# SDI.net
KiCad netlist of a schematic drawn in Altium Designer
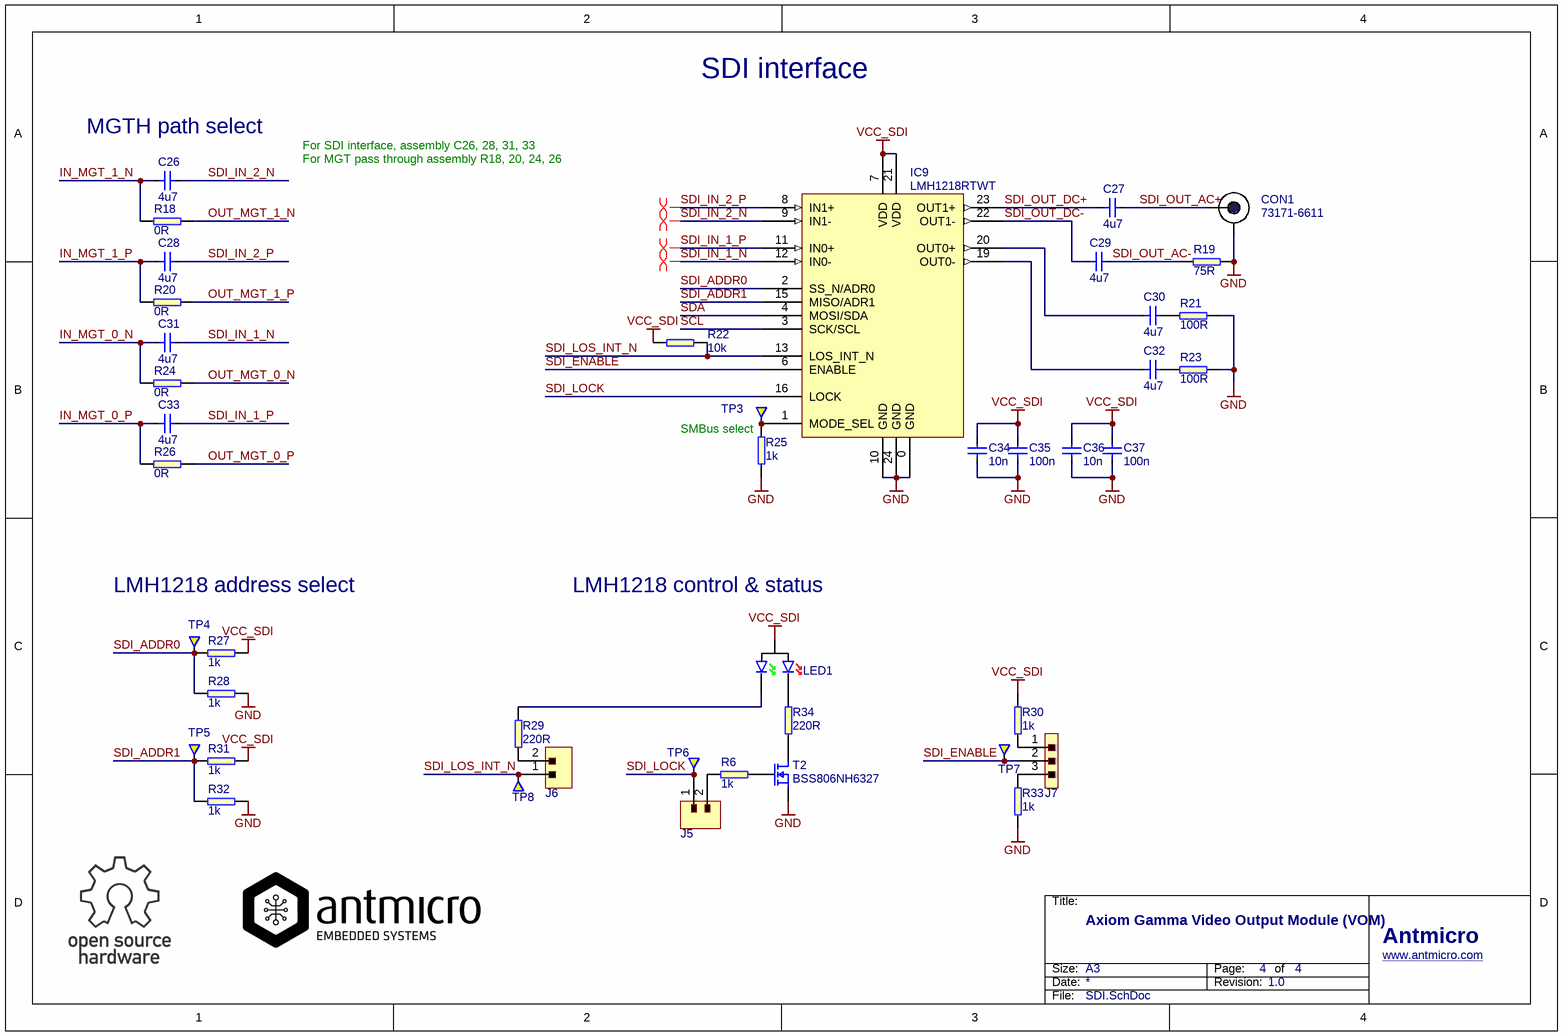
[diagram p0: SDI.SchDoc]

(export (version "E")
  (design (tool "Eeschema 10.0.6"))
  (components
    (comp (ref "C26")
      (value "4u7")
      (footprint "0402")
      (description "MLCC SMT Capacitor 0402")
      (fields (field (name "PART NUMBER") "C_4u7_0402") (field (name "MANUFACTURER") "MURATA"))
      (libsource (lib "VOM") (part "C_4u7_0402"))
    )
    (comp (ref "C27")
      (value "4u7")
      (footprint "0402")
      (description "MLCC SMT Capacitor 0402")
      (fields (field (name "PART NUMBER") "C_4u7_0402") (field (name "MANUFACTURER") "MURATA"))
      (libsource (lib "VOM") (part "C_4u7_0402"))
    )
    (comp (ref "C28")
      (value "4u7")
      (footprint "0402")
      (description "MLCC SMT Capacitor 0402")
      (fields (field (name "PART NUMBER") "C_4u7_0402") (field (name "MANUFACTURER") "MURATA"))
      (libsource (lib "VOM") (part "C_4u7_0402"))
    )
    (comp (ref "C29")
      (value "4u7")
      (footprint "0402")
      (description "MLCC SMT Capacitor 0402")
      (fields (field (name "PART NUMBER") "C_4u7_0402") (field (name "MANUFACTURER") "MURATA"))
      (libsource (lib "VOM") (part "C_4u7_0402"))
    )
    (comp (ref "C30")
      (value "4u7")
      (footprint "0402")
      (description "MLCC SMT Capacitor 0402")
      (fields (field (name "PART NUMBER") "C_4u7_0402") (field (name "MANUFACTURER") "MURATA"))
      (libsource (lib "VOM") (part "C_4u7_0402"))
    )
    (comp (ref "C31")
      (value "4u7")
      (footprint "0402")
      (description "MLCC SMT Capacitor 0402")
      (fields (field (name "PART NUMBER") "C_4u7_0402") (field (name "MANUFACTURER") "MURATA"))
      (libsource (lib "VOM") (part "C_4u7_0402"))
    )
    (comp (ref "C32")
      (value "4u7")
      (footprint "0402")
      (description "MLCC SMT Capacitor 0402")
      (fields (field (name "PART NUMBER") "C_4u7_0402") (field (name "MANUFACTURER") "MURATA"))
      (libsource (lib "VOM") (part "C_4u7_0402"))
    )
    (comp (ref "C33")
      (value "4u7")
      (footprint "0402")
      (description "MLCC SMT Capacitor 0402")
      (fields (field (name "PART NUMBER") "C_4u7_0402") (field (name "MANUFACTURER") "MURATA"))
      (libsource (lib "VOM") (part "C_4u7_0402"))
    )
    (comp (ref "C34")
      (value "10n")
      (footprint "0402")
      (description "MLCC SMT Capacitor 0402")
      (fields (field (name "PART NUMBER") "C_10n_0402") (field (name "MANUFACTURER") "AVX"))
      (libsource (lib "VOM") (part "C_10n_0402"))
    )
    (comp (ref "C35")
      (value "100n")
      (footprint "0402")
      (description "MLCC SMT Capacitor 0402")
      (fields (field (name "PART NUMBER") "C_100n_0402") (field (name "MANUFACTURER") "MULTICOMP"))
      (libsource (lib "VOM") (part "C_100n_0402"))
    )
    (comp (ref "C36")
      (value "10n")
      (footprint "0402")
      (description "MLCC SMT Capacitor 0402")
      (fields (field (name "PART NUMBER") "C_10n_0402") (field (name "MANUFACTURER") "AVX"))
      (libsource (lib "VOM") (part "C_10n_0402"))
    )
    (comp (ref "C37")
      (value "100n")
      (footprint "0402")
      (description "MLCC SMT Capacitor 0402")
      (fields (field (name "PART NUMBER") "C_100n_0402") (field (name "MANUFACTURER") "MULTICOMP"))
      (libsource (lib "VOM") (part "C_100n_0402"))
    )
    (comp (ref "CON1")
      (value "73171-6611")
      (footprint "MOLEX_BNC_73171-6611")
      (fields (field (name "PART NUMBER") "MOLEX_BNC_73171-6611") (field (name "MANUFACTURER") "MOLEX"))
      (libsource (lib "VOM") (part "COAXIAL"))
    )
    (comp (ref "IC9")
      (value "LMH1218RTWT")
      (footprint "WQFN-24")
      (description "Low Power Ultra HD Cable Driver with Integrated Reclocker")
      (fields (field (name "MANUFACTURER") "TEXAS INSTRUMENTS"))
      (libsource (lib "VOM") (part "LMH1218"))
    )
    (comp (ref "J5")
      (value "MH_1X02_2.54")
      (footprint "MH_1X02_2.54")
      (description "Male header, 1 x 02 pins, pitch 2.54 mm")
      (fields (field (name "MANUFACTURER") "MULTICOMP"))
      (libsource (lib "") (part "1X02_1"))
    )
    (comp (ref "J6")
      (value "MH_1X02_2.54")
      (footprint "MH_1X02_2.54")
      (description "Male header, 1 x 02 pins, pitch 2.54 mm")
      (fields (field (name "MANUFACTURER") "MULTICOMP"))
      (libsource (lib "VOM") (part "1X02"))
    )
    (comp (ref "J7")
      (value "MH_1X03_2.54")
      (footprint "MH_1X03_2.54")
      (description "Male header, 1 x 03 pins, pitch 2.54 mm")
      (fields (field (name "MANUFACTURER") "HARWIN"))
      (libsource (lib "VOM") (part "1X03_1"))
    )
    (comp (ref "LED1")
      (value "LED-LiteON-LTST-S326KGJRKT")
      (footprint "LED-LiteON-LTST-S326KGJRKT")
      (description "Standard LEDs - SMD Green/Red Clear 571nm/631nm")
      (fields (field (name "MANUFACTURER") "Lite-On"))
      (libsource (lib "VOM") (part "LED-LiteON-LTST-S326KGJRKT"))
    )
    (comp (ref "R6")
      (value "1k")
      (footprint "0603")
      (description "SMT Resistor 0R 0603")
      (fields (field (name "PART NUMBER") "R_1k_0603") (field (name "MANUFACTURER") "BOURNS"))
      (libsource (lib "VOM") (part "R_1k_0603"))
    )
    (comp (ref "R18")
      (value "0R")
      (footprint "0402")
      (description "SMT Resistor 0402")
      (fields (field (name "PART NUMBER") "R_0R_0402") (field (name "MANUFACTURER") "MULTICOMP"))
      (libsource (lib "VOM") (part "R_0R_0402"))
    )
    (comp (ref "R19")
      (value "75R")
      (footprint "0402")
      (description "SMT Resistor 0402")
      (fields (field (name "PART NUMBER") "R_75R_0402") (field (name "MANUFACTURER") "YAGEO(PHYCOMP)"))
      (libsource (lib "VOM") (part "R_75R_0402"))
    )
    (comp (ref "R20")
      (value "0R")
      (footprint "0402")
      (description "SMT Resistor 0402")
      (fields (field (name "PART NUMBER") "R_0R_0402") (field (name "MANUFACTURER") "MULTICOMP"))
      (libsource (lib "VOM") (part "R_0R_0402"))
    )
    (comp (ref "R21")
      (value "100R")
      (footprint "0402")
      (description "SMT Resistor 0402")
      (fields (field (name "PART NUMBER") "R_100R_0402") (field (name "MANUFACTURER") "BOURNS"))
      (libsource (lib "VOM") (part "R_100R_0402"))
    )
    (comp (ref "R22")
      (value "10k")
      (footprint "0402")
      (description "SMT Resistor 0402")
      (fields (field (name "PART NUMBER") "R_10k_0402") (field (name "MANUFACTURER") "MULTICOMP"))
      (libsource (lib "VOM") (part "R_10k_0402"))
    )
    (comp (ref "R23")
      (value "100R")
      (footprint "0402")
      (description "SMT Resistor 0402")
      (fields (field (name "PART NUMBER") "R_100R_0402") (field (name "MANUFACTURER") "BOURNS"))
      (libsource (lib "VOM") (part "R_100R_0402"))
    )
    (comp (ref "R24")
      (value "0R")
      (footprint "0402")
      (description "SMT Resistor 0402")
      (fields (field (name "PART NUMBER") "R_0R_0402") (field (name "MANUFACTURER") "MULTICOMP"))
      (libsource (lib "VOM") (part "R_0R_0402"))
    )
    (comp (ref "R25")
      (value "1k")
      (footprint "0402")
      (description "SMT Resistor 0402")
      (fields (field (name "PART NUMBER") "R_1k_0402") (field (name "MANUFACTURER") "MULTICOMP"))
      (libsource (lib "VOM") (part "R_1k_0402"))
    )
    (comp (ref "R26")
      (value "0R")
      (footprint "0402")
      (description "SMT Resistor 0402")
      (fields (field (name "PART NUMBER") "R_0R_0402") (field (name "MANUFACTURER") "MULTICOMP"))
      (libsource (lib "VOM") (part "R_0R_0402"))
    )
    (comp (ref "R27")
      (value "1k")
      (footprint "0603")
      (description "SMT Resistor 0R 0603")
      (fields (field (name "PART NUMBER") "R_1k_0603") (field (name "MANUFACTURER") "BOURNS"))
      (libsource (lib "VOM") (part "R_1k_0603"))
    )
    (comp (ref "R28")
      (value "1k")
      (footprint "0603")
      (description "SMT Resistor 0R 0603")
      (fields (field (name "PART NUMBER") "R_1k_0603") (field (name "MANUFACTURER") "BOURNS"))
      (libsource (lib "VOM") (part "R_1k_0603"))
    )
    (comp (ref "R29")
      (value "220R")
      (footprint "0402")
      (description "SMT Resistor 0402")
      (fields (field (name "PART NUMBER") "R_220R_0402") (field (name "MANUFACTURER") "TE CONNECTIVITY"))
      (libsource (lib "VOM") (part "R_220R_0402"))
    )
    (comp (ref "R30")
      (value "1k")
      (footprint "0603")
      (description "SMT Resistor 0R 0603")
      (fields (field (name "PART NUMBER") "R_1k_0603") (field (name "MANUFACTURER") "BOURNS"))
      (libsource (lib "") (part "R_1k_0603_1"))
    )
    (comp (ref "R31")
      (value "1k")
      (footprint "0603")
      (description "SMT Resistor 0R 0603")
      (fields (field (name "PART NUMBER") "R_1k_0603") (field (name "MANUFACTURER") "BOURNS"))
      (libsource (lib "VOM") (part "R_1k_0603"))
    )
    (comp (ref "R32")
      (value "1k")
      (footprint "0603")
      (description "SMT Resistor 0R 0603")
      (fields (field (name "PART NUMBER") "R_1k_0603") (field (name "MANUFACTURER") "BOURNS"))
      (libsource (lib "VOM") (part "R_1k_0603"))
    )
    (comp (ref "R33")
      (value "1k")
      (footprint "0603")
      (description "SMT Resistor 0R 0603")
      (fields (field (name "PART NUMBER") "R_1k_0603") (field (name "MANUFACTURER") "BOURNS"))
      (libsource (lib "") (part "R_1k_0603_1"))
    )
    (comp (ref "R34")
      (value "220R")
      (footprint "0402")
      (description "SMT Resistor 0402")
      (fields (field (name "PART NUMBER") "R_220R_0402") (field (name "MANUFACTURER") "TE CONNECTIVITY"))
      (libsource (lib "") (part "R_220R_0402_1"))
    )
    (comp (ref "T2")
      (value "BSS806NH6327")
      (footprint "SOT-23")
      (description "MOSFET, BRT, N CH, 2.3 A, 20 V, 0.041 ohm, 2.5 V, 550 mV")
      (fields (field (name "MANUFACTURER") "INFINEON"))
      (libsource (lib "VOM") (part "BSS806NH6327"))
    )
    (comp (ref "TP3")
      (value "Testpad")
      (footprint "Testpad")
      (description "Testpad 2mm diameter")
      (fields (field (name "MANUFACTURER") "PCB ONLY"))
      (libsource (lib "VOM") (part "Testpad"))
    )
    (comp (ref "TP4")
      (value "Testpad")
      (footprint "Testpad")
      (description "Testpad 2mm diameter")
      (fields (field (name "MANUFACTURER") "PCB ONLY"))
      (libsource (lib "VOM") (part "Testpad"))
    )
    (comp (ref "TP5")
      (value "Testpad")
      (footprint "Testpad")
      (description "Testpad 2mm diameter")
      (fields (field (name "MANUFACTURER") "PCB ONLY"))
      (libsource (lib "VOM") (part "Testpad"))
    )
    (comp (ref "TP6")
      (value "Testpad")
      (footprint "Testpad")
      (description "Testpad 2mm diameter")
      (fields (field (name "MANUFACTURER") "PCB ONLY"))
      (libsource (lib "VOM") (part "Testpad"))
    )
    (comp (ref "TP7")
      (value "Testpad")
      (footprint "Testpad")
      (description "Testpad 2mm diameter")
      (fields (field (name "MANUFACTURER") "PCB ONLY"))
      (libsource (lib "VOM") (part "Testpad"))
    )
    (comp (ref "TP8")
      (value "Testpad")
      (footprint "Testpad")
      (description "Testpad 2mm diameter")
      (fields (field (name "MANUFACTURER") "PCB ONLY"))
      (libsource (lib "VOM") (part "Testpad"))
    )
  )
  (nets
    (net (code "1") (name "/IN_MGT_0_N") (class "Default")
      (node (ref "C31") (pin "1") (pinfunction "1_1") (pintype "passive"))
      (node (ref "R24") (pin "1") (pintype "passive"))
    )
    (net (code "2") (name "/IN_MGT_0_P") (class "Default")
      (node (ref "C33") (pin "1") (pinfunction "1_1") (pintype "passive"))
      (node (ref "R26") (pin "1") (pintype "passive"))
    )
    (net (code "3") (name "/IN_MGT_1_N") (class "Default")
      (node (ref "C26") (pin "1") (pinfunction "1_1") (pintype "passive"))
      (node (ref "R18") (pin "1") (pintype "passive"))
    )
    (net (code "4") (name "/IN_MGT_1_P") (class "Default")
      (node (ref "C28") (pin "1") (pinfunction "1_1") (pintype "passive"))
      (node (ref "R20") (pin "1") (pintype "passive"))
    )
    (net (code "5") (name "/OUT_MGT_0_N") (class "Default") (node (ref "R24") (pin "2") (pintype "passive")))
    (net (code "6") (name "/OUT_MGT_0_P") (class "Default") (node (ref "R26") (pin "2") (pintype "passive")))
    (net (code "7") (name "/OUT_MGT_1_N") (class "Default") (node (ref "R18") (pin "2") (pintype "passive")))
    (net (code "8") (name "/OUT_MGT_1_P") (class "Default") (node (ref "R20") (pin "2") (pintype "passive")))
    (net (code "9") (name "/SCL") (class "Default")
      (node (ref "IC9") (pin "3") (pinfunction "SCK/SCL_3") (pintype "passive"))
    )
    (net (code "10") (name "/SDA") (class "Default")
      (node (ref "IC9") (pin "4") (pinfunction "MOSI/SDA_4") (pintype "passive"))
    )
    (net (code "11") (name "/SDI_ADDR0") (class "Default")
      (node (ref "IC9") (pin "2") (pinfunction "SS_N/ADR0_2") (pintype "passive"))
      (node (ref "R27") (pin "1") (pintype "passive"))
      (node (ref "R28") (pin "1") (pintype "passive"))
      (node (ref "TP4") (pin "1") (pintype "passive"))
    )
    (net (code "12") (name "/SDI_ADDR1") (class "Default")
      (node (ref "IC9") (pin "15") (pinfunction "MISO/ADR1_15") (pintype "passive"))
      (node (ref "R31") (pin "1") (pintype "passive"))
      (node (ref "R32") (pin "1") (pintype "passive"))
      (node (ref "TP5") (pin "1") (pintype "passive"))
    )
    (net (code "13") (name "/SDI_ENABLE") (class "Default")
      (node (ref "IC9") (pin "6") (pinfunction "ENABLE_6") (pintype "passive"))
      (node (ref "J7") (pin "2") (pinfunction "2_2") (pintype "passive"))
      (node (ref "TP7") (pin "1") (pintype "passive"))
    )
    (net (code "14") (name "/SDI_IN_1_N") (class "Default")
      (node (ref "C31") (pin "2") (pinfunction "2_2") (pintype "passive"))
      (node (ref "IC9") (pin "12") (pinfunction "IN0-_12") (pintype "input"))
    )
    (net (code "15") (name "/SDI_IN_1_P") (class "Default")
      (node (ref "C33") (pin "2") (pinfunction "2_2") (pintype "passive"))
      (node (ref "IC9") (pin "11") (pinfunction "IN0+_11") (pintype "input"))
    )
    (net (code "16") (name "/SDI_IN_2_N") (class "Default")
      (node (ref "C26") (pin "2") (pinfunction "2_2") (pintype "passive"))
      (node (ref "IC9") (pin "9") (pinfunction "IN1-_9") (pintype "input"))
    )
    (net (code "17") (name "/SDI_IN_2_P") (class "Default")
      (node (ref "C28") (pin "2") (pinfunction "2_2") (pintype "passive"))
      (node (ref "IC9") (pin "8") (pinfunction "IN1+_8") (pintype "input"))
    )
    (net (code "18") (name "/SDI_LOCK") (class "Default")
      (node (ref "IC9") (pin "16") (pinfunction "LOCK_16") (pintype "passive"))
      (node (ref "J5") (pin "1") (pinfunction "1_1") (pintype "passive"))
      (node (ref "TP6") (pin "1") (pintype "passive"))
    )
    (net (code "19") (name "/SDI_LOS_INT_N") (class "Default")
      (node (ref "IC9") (pin "13") (pinfunction "LOS_INT_N_13") (pintype "passive"))
      (node (ref "J6") (pin "1") (pinfunction "1_1") (pintype "passive"))
      (node (ref "R22") (pin "2") (pintype "passive"))
      (node (ref "TP8") (pin "1") (pintype "passive"))
    )
    (net (code "20") (name "/SDI_OUT_AC+") (class "Default")
      (node (ref "C27") (pin "2") (pinfunction "2_2") (pintype "passive"))
      (node (ref "CON1") (pin "1") (pinfunction "1_1") (pintype "passive"))
    )
    (net (code "21") (name "/SDI_OUT_AC-") (class "Default")
      (node (ref "C29") (pin "2") (pinfunction "2_2") (pintype "passive"))
      (node (ref "R19") (pin "2") (pintype "passive"))
    )
    (net (code "22") (name "/SDI_OUT_DC+") (class "Default")
      (node (ref "C27") (pin "1") (pinfunction "1_1") (pintype "passive"))
      (node (ref "IC9") (pin "23") (pinfunction "OUT1+_23") (pintype "output"))
    )
    (net (code "23") (name "/SDI_OUT_DC-") (class "Default")
      (node (ref "C29") (pin "1") (pinfunction "1_1") (pintype "passive"))
      (node (ref "IC9") (pin "22") (pinfunction "OUT1-_22") (pintype "output"))
    )
    (net (code "24") (name "GND") (class "Default")
      (node (ref "C34") (pin "1") (pinfunction "1_1") (pintype "passive"))
      (node (ref "C35") (pin "1") (pinfunction "1_1") (pintype "passive"))
      (node (ref "C36") (pin "1") (pinfunction "1_1") (pintype "passive"))
      (node (ref "C37") (pin "1") (pinfunction "1_1") (pintype "passive"))
      (node (ref "CON1") (pin "S") (pinfunction "S_S") (pintype "passive"))
      (node (ref "IC9") (pin "0") (pinfunction "GND_0") (pintype "passive"))
      (node (ref "IC9") (pin "10") (pinfunction "GND_10") (pintype "passive"))
      (node (ref "IC9") (pin "24") (pinfunction "GND_24") (pintype "passive"))
      (node (ref "R19") (pin "1") (pintype "passive"))
      (node (ref "R21") (pin "1") (pintype "passive"))
      (node (ref "R23") (pin "1") (pintype "passive"))
      (node (ref "R25") (pin "1") (pintype "passive"))
      (node (ref "R28") (pin "2") (pintype "passive"))
      (node (ref "R32") (pin "2") (pintype "passive"))
      (node (ref "R33") (pin "2") (pintype "passive"))
      (node (ref "T2") (pin "2") (pinfunction "S_2") (pintype "passive"))
    )
    (net (code "25") (name "Net-(C30-Pad2)") (class "Default")
      (node (ref "C30") (pin "2") (pinfunction "2_2") (pintype "passive"))
      (node (ref "R21") (pin "2") (pintype "passive"))
    )
    (net (code "26") (name "Net-(C32-Pad2)") (class "Default")
      (node (ref "C32") (pin "2") (pinfunction "2_2") (pintype "passive"))
      (node (ref "R23") (pin "2") (pintype "passive"))
    )
    (net (code "27") (name "Net-(IC9-MODE_SEL)") (class "Default")
      (node (ref "IC9") (pin "1") (pinfunction "MODE_SEL_1") (pintype "passive"))
      (node (ref "R25") (pin "2") (pintype "passive"))
      (node (ref "TP3") (pin "1") (pintype "passive"))
    )
    (net (code "28") (name "Net-(IC9-OUT0+)") (class "Default")
      (node (ref "C30") (pin "1") (pinfunction "1_1") (pintype "passive"))
      (node (ref "IC9") (pin "20") (pinfunction "OUT0+_20") (pintype "output"))
    )
    (net (code "29") (name "Net-(IC9-OUT0-)") (class "Default")
      (node (ref "C32") (pin "1") (pinfunction "1_1") (pintype "passive"))
      (node (ref "IC9") (pin "19") (pinfunction "OUT0-_19") (pintype "output"))
    )
    (net (code "30") (name "Net-(J5-Pad2)") (class "Default")
      (node (ref "J5") (pin "2") (pinfunction "2_2") (pintype "passive"))
      (node (ref "R6") (pin "1") (pintype "passive"))
    )
    (net (code "31") (name "Net-(J6-Pad2)") (class "Default")
      (node (ref "J6") (pin "2") (pinfunction "2_2") (pintype "passive"))
      (node (ref "R29") (pin "2") (pintype "passive"))
    )
    (net (code "32") (name "Net-(J7-Pad1)") (class "Default")
      (node (ref "J7") (pin "1") (pinfunction "1_1") (pintype "passive"))
      (node (ref "R30") (pin "2") (pintype "passive"))
    )
    (net (code "33") (name "Net-(J7-Pad3)") (class "Default")
      (node (ref "J7") (pin "3") (pinfunction "3_3") (pintype "passive"))
      (node (ref "R33") (pin "1") (pintype "passive"))
    )
    (net (code "34") (name "Net-(LED1-PadC1)") (class "Default")
      (node (ref "LED1") (pin "C1") (pinfunction "C1_C1") (pintype "passive"))
      (node (ref "R34") (pin "2") (pintype "passive"))
    )
    (net (code "35") (name "Net-(LED1-PadC2)") (class "Default")
      (node (ref "LED1") (pin "C2") (pinfunction "C2_C2") (pintype "passive"))
      (node (ref "R29") (pin "1") (pintype "passive"))
    )
    (net (code "36") (name "Net-(T2-D)") (class "Default")
      (node (ref "R34") (pin "1") (pintype "passive"))
      (node (ref "T2") (pin "3") (pinfunction "D_3") (pintype "passive"))
    )
    (net (code "37") (name "Net-(T2-G)") (class "Default")
      (node (ref "R6") (pin "2") (pintype "passive"))
      (node (ref "T2") (pin "1") (pinfunction "G_1") (pintype "passive"))
    )
    (net (code "38") (name "VCC_SDI") (class "Default")
      (node (ref "C34") (pin "2") (pinfunction "2_2") (pintype "passive"))
      (node (ref "C35") (pin "2") (pinfunction "2_2") (pintype "passive"))
      (node (ref "C36") (pin "2") (pinfunction "2_2") (pintype "passive"))
      (node (ref "C37") (pin "2") (pinfunction "2_2") (pintype "passive"))
      (node (ref "IC9") (pin "21") (pinfunction "VDD_21") (pintype "passive"))
      (node (ref "IC9") (pin "7") (pinfunction "VDD_7") (pintype "passive"))
      (node (ref "LED1") (pin "A") (pinfunction "A_A") (pintype "passive"))
      (node (ref "R22") (pin "1") (pintype "passive"))
      (node (ref "R27") (pin "2") (pintype "passive"))
      (node (ref "R30") (pin "1") (pintype "passive"))
      (node (ref "R31") (pin "2") (pintype "passive"))
    )
  )
)
